# KEYPAD.net
KiCad netlist of a schematic drawn in Altium Designer
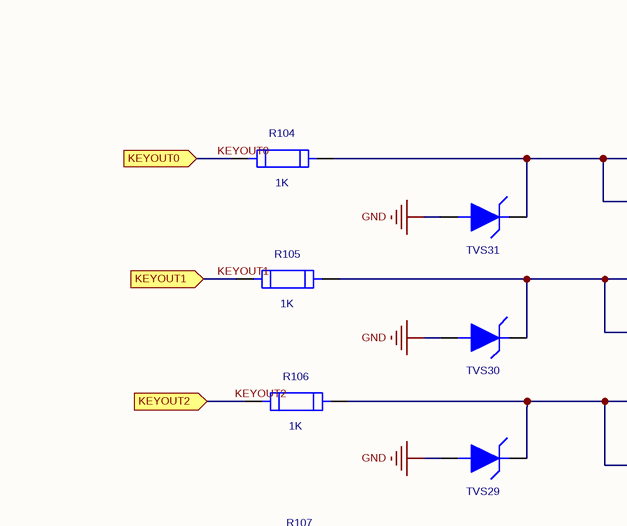
[diagram p0: KEYPAD.SchDoc, top left]
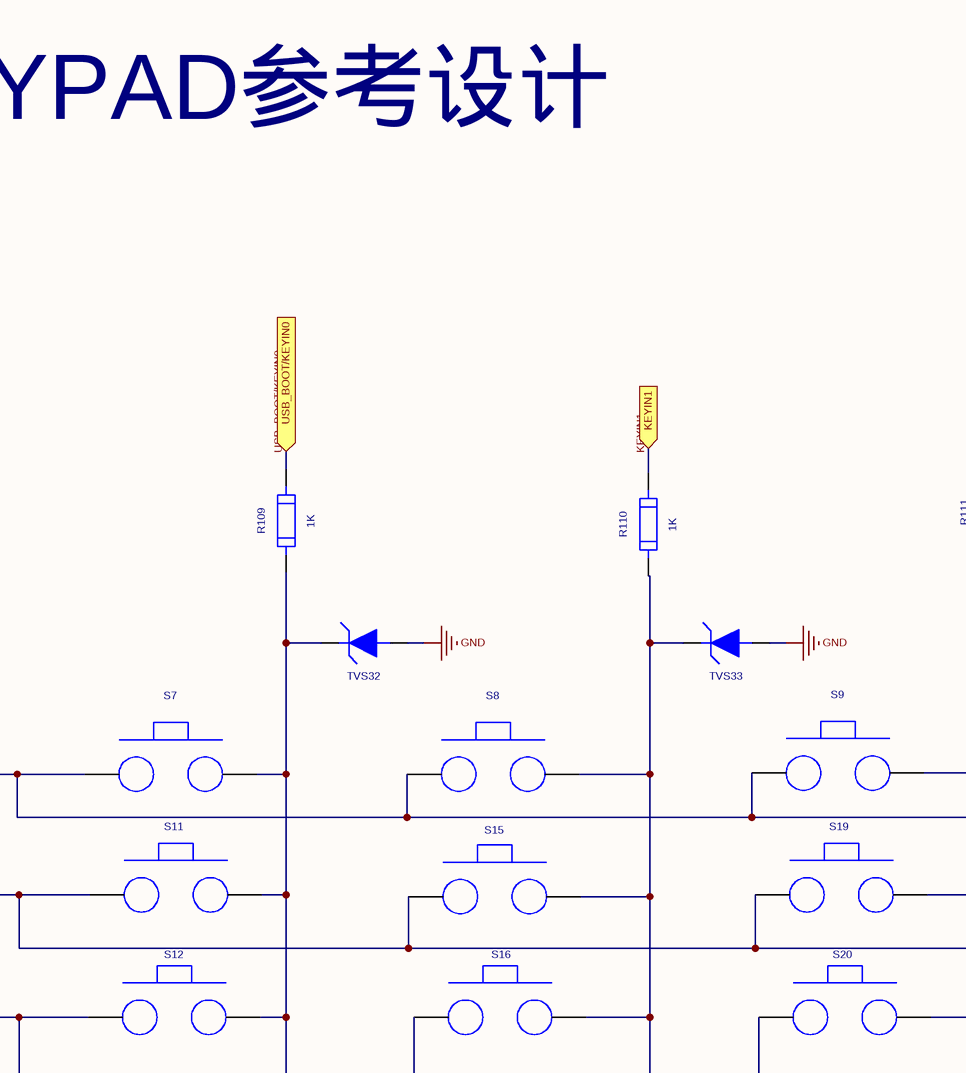
[diagram p1: KEYPAD.SchDoc, top middle]
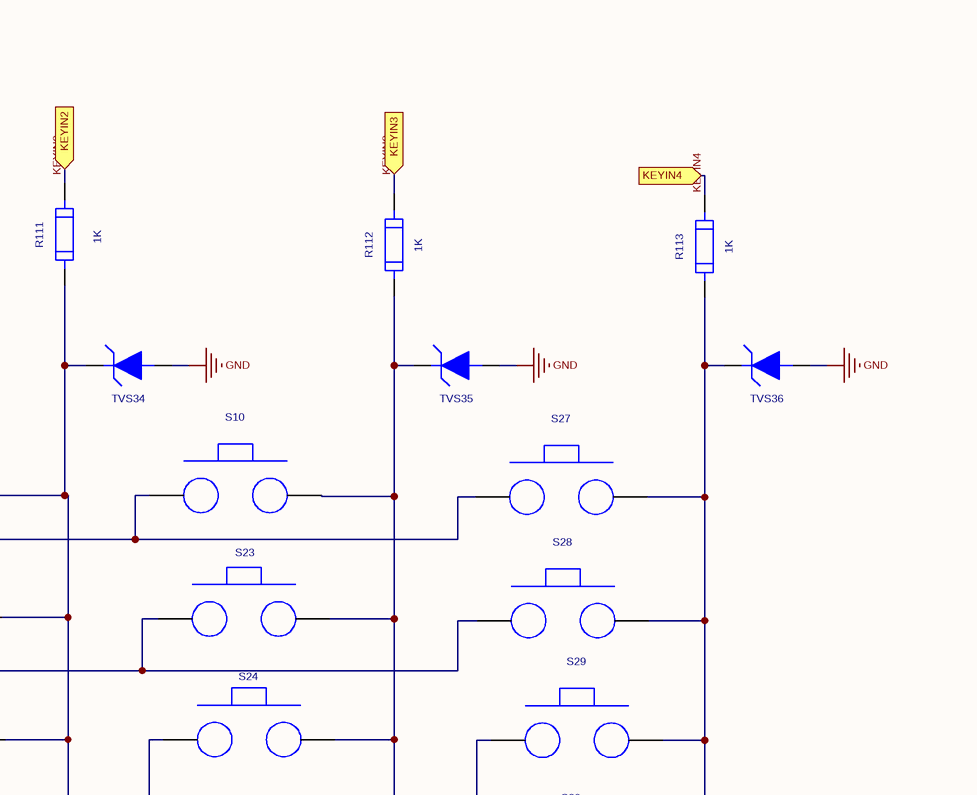
[diagram p2: KEYPAD.SchDoc, top right]
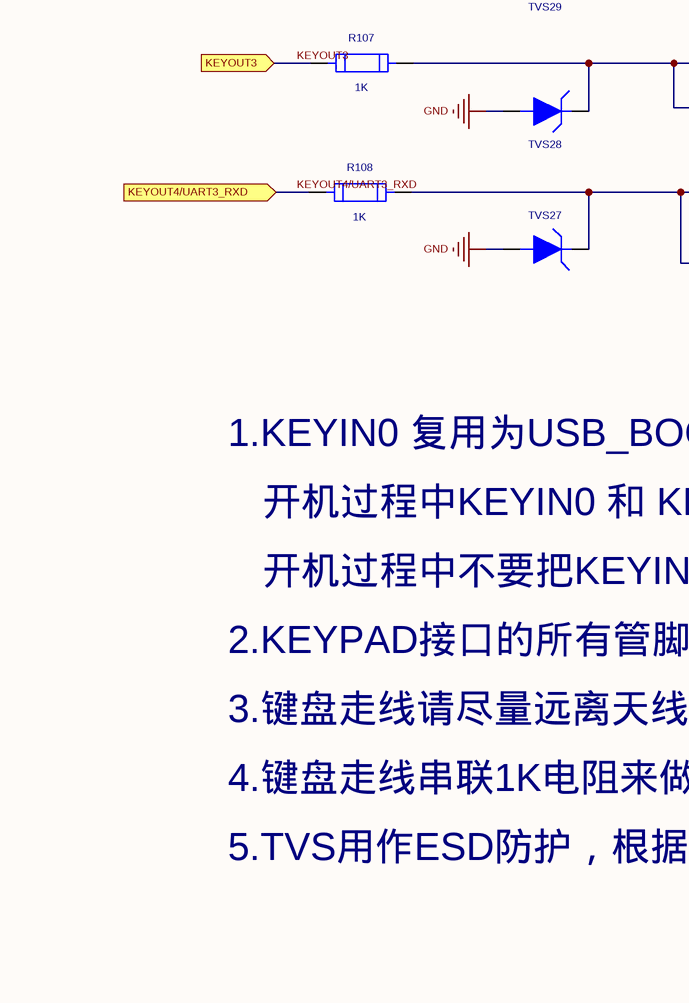
[diagram p3: KEYPAD.SchDoc, bottom left]
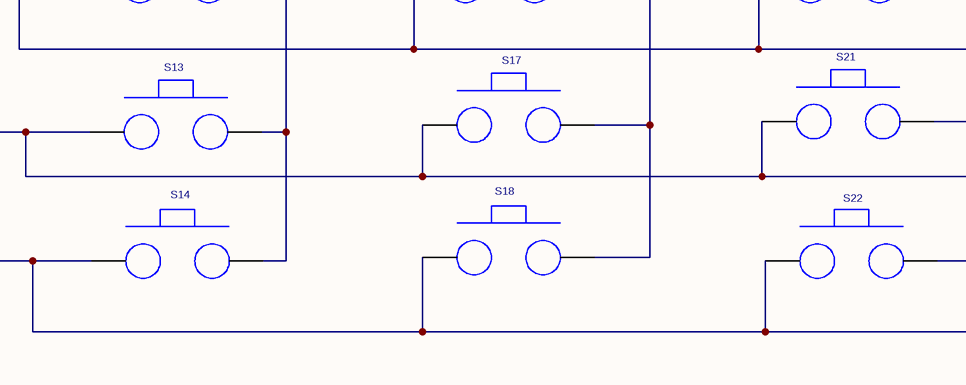
[diagram p4: KEYPAD.SchDoc, bottom middle]
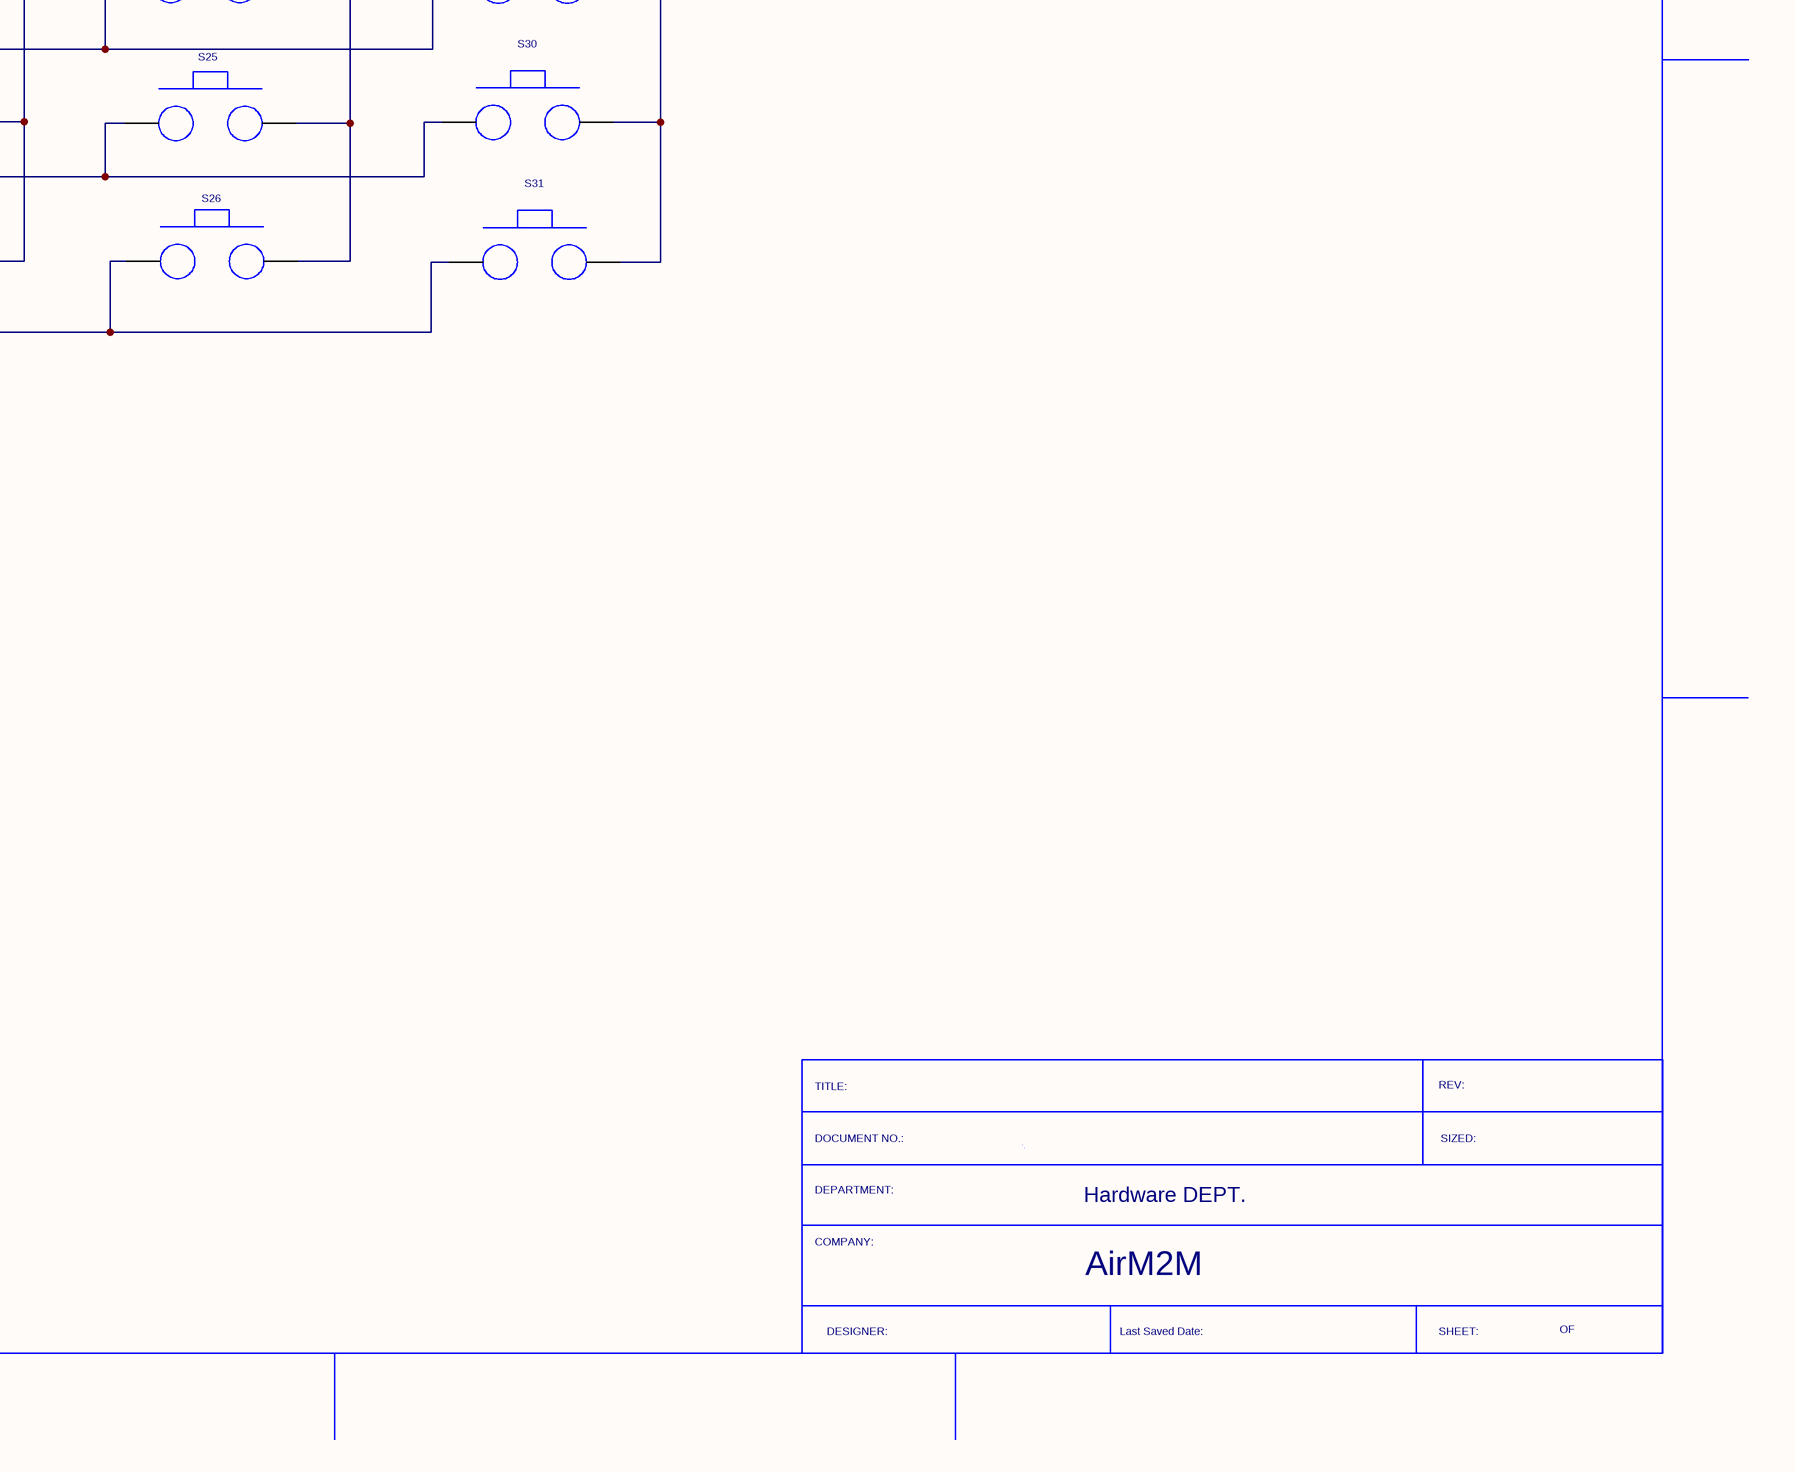
[diagram p5: KEYPAD.SchDoc, bottom right]

(export (version "E")
  (design (tool "Eeschema 10.0.6"))
  (components
    (comp (ref "R104")
      (value "1K")
      (footprint "SR0402")
      (description "RES FILM;1K;+/-1%;1/16W;0402;0.4mm;ROHS")
      (fields (field (name "TOLERANCE") "+/-1%") (field (name "Comment") "RES-1K-+-1%-0402"))
      (libsource (lib "*") (part "RES-1K-+-1%-0402"))
    )
    (comp (ref "R105")
      (value "1K")
      (footprint "SR0402")
      (description "RES FILM;1K;+/-1%;1/16W;0402;0.4mm;ROHS")
      (fields (field (name "TOLERANCE") "+/-1%") (field (name "Comment") "RES-1K-+-1%-0402"))
      (libsource (lib "*") (part "RES-1K-+-1%-0402"))
    )
    (comp (ref "R106")
      (value "1K")
      (footprint "SR0402")
      (description "RES FILM;1K;+/-1%;1/16W;0402;0.4mm;ROHS")
      (fields (field (name "TOLERANCE") "+/-1%") (field (name "Comment") "RES-1K-+-1%-0402"))
      (libsource (lib "*") (part "RES-1K-+-1%-0402"))
    )
    (comp (ref "R107")
      (value "1K")
      (footprint "SR0402")
      (description "RES FILM;1K;+/-1%;1/16W;0402;0.4mm;ROHS")
      (fields (field (name "TOLERANCE") "+/-1%") (field (name "Comment") "RES-1K-+-1%-0402"))
      (libsource (lib "*") (part "RES-1K-+-1%-0402"))
    )
    (comp (ref "R108")
      (value "1K")
      (footprint "SR0402")
      (description "RES FILM;1K;+/-1%;1/16W;0402;0.4mm;ROHS")
      (fields (field (name "TOLERANCE") "+/-1%") (field (name "Comment") "RES-1K-+-1%-0402"))
      (libsource (lib "*") (part "RES-1K-+-1%-0402"))
    )
    (comp (ref "R109")
      (value "1K")
      (footprint "SR0402")
      (description "RES FILM;1K;+/-1%;1/16W;0402;0.4mm;ROHS")
      (fields (field (name "TOLERANCE") "+/-1%") (field (name "Comment") "RES-1K-+-1%-0402"))
      (libsource (lib "*") (part "RES-1K-+-1%-0402"))
    )
    (comp (ref "R110")
      (value "1K")
      (footprint "SR0402")
      (description "RES FILM;1K;+/-1%;1/16W;0402;0.4mm;ROHS")
      (fields (field (name "TOLERANCE") "+/-1%") (field (name "Comment") "RES-1K-+-1%-0402"))
      (libsource (lib "*") (part "RES-1K-+-1%-0402"))
    )
    (comp (ref "R111")
      (value "1K")
      (footprint "SR0402")
      (description "RES FILM;1K;+/-1%;1/16W;0402;0.4mm;ROHS")
      (fields (field (name "TOLERANCE") "+/-1%") (field (name "Comment") "RES-1K-+-1%-0402"))
      (libsource (lib "*") (part "RES-1K-+-1%-0402"))
    )
    (comp (ref "R112")
      (value "1K")
      (footprint "SR0402")
      (description "RES FILM;1K;+/-1%;1/16W;0402;0.4mm;ROHS")
      (fields (field (name "TOLERANCE") "+/-1%") (field (name "Comment") "RES-1K-+-1%-0402"))
      (libsource (lib "*") (part "RES-1K-+-1%-0402"))
    )
    (comp (ref "R113")
      (value "1K")
      (footprint "SR0402")
      (description "RES FILM;1K;+/-1%;1/16W;0402;0.4mm;ROHS")
      (fields (field (name "TOLERANCE") "+/-1%") (field (name "Comment") "RES-1K-+-1%-0402"))
      (libsource (lib "*") (part "RES-1K-+-1%-0402"))
    )
    (comp (ref "S7")
      (value "KEYPAD-D5X5")
      (footprint "KEY55")
      (description "SWITCH-KEYPAD")
      (libsource (lib "*") (part "KEYPAD-D5X5"))
    )
    (comp (ref "S8")
      (value "KEYPAD-D5X5")
      (footprint "KEY55")
      (description "SWITCH-KEYPAD")
      (libsource (lib "*") (part "KEYPAD-D5X5"))
    )
    (comp (ref "S9")
      (value "KEYPAD-D5X5")
      (footprint "KEY55")
      (description "SWITCH-KEYPAD")
      (libsource (lib "*") (part "KEYPAD-D5X5"))
    )
    (comp (ref "S10")
      (value "KEYPAD-D5X5")
      (footprint "KEY55")
      (description "SWITCH-KEYPAD")
      (libsource (lib "*") (part "KEYPAD-D5X5"))
    )
    (comp (ref "S11")
      (value "KEYPAD-D5X5")
      (footprint "KEY55")
      (description "SWITCH-KEYPAD")
      (libsource (lib "*") (part "KEYPAD-D5X5"))
    )
    (comp (ref "S12")
      (value "KEYPAD-D5X5")
      (footprint "KEY55")
      (description "SWITCH-KEYPAD")
      (libsource (lib "*") (part "KEYPAD-D5X5"))
    )
    (comp (ref "S13")
      (value "KEYPAD-D5X5")
      (footprint "KEY55")
      (description "SWITCH-KEYPAD")
      (libsource (lib "*") (part "KEYPAD-D5X5"))
    )
    (comp (ref "S14")
      (value "KEYPAD-D5X5")
      (footprint "KEY55")
      (description "SWITCH-KEYPAD")
      (libsource (lib "*") (part "KEYPAD-D5X5"))
    )
    (comp (ref "S15")
      (value "KEYPAD-D5X5")
      (footprint "KEY55")
      (description "SWITCH-KEYPAD")
      (libsource (lib "*") (part "KEYPAD-D5X5"))
    )
    (comp (ref "S16")
      (value "KEYPAD-D5X5")
      (footprint "KEY55")
      (description "SWITCH-KEYPAD")
      (libsource (lib "*") (part "KEYPAD-D5X5"))
    )
    (comp (ref "S17")
      (value "KEYPAD-D5X5")
      (footprint "KEY55")
      (description "SWITCH-KEYPAD")
      (libsource (lib "*") (part "KEYPAD-D5X5"))
    )
    (comp (ref "S18")
      (value "KEYPAD-D5X5")
      (footprint "KEY55")
      (description "SWITCH-KEYPAD")
      (libsource (lib "*") (part "KEYPAD-D5X5"))
    )
    (comp (ref "S19")
      (value "KEYPAD-D5X5")
      (footprint "KEY55")
      (description "SWITCH-KEYPAD")
      (libsource (lib "*") (part "KEYPAD-D5X5"))
    )
    (comp (ref "S20")
      (value "KEYPAD-D5X5")
      (footprint "KEY55")
      (description "SWITCH-KEYPAD")
      (libsource (lib "*") (part "KEYPAD-D5X5"))
    )
    (comp (ref "S21")
      (value "KEYPAD-D5X5")
      (footprint "KEY55")
      (description "SWITCH-KEYPAD")
      (libsource (lib "*") (part "KEYPAD-D5X5"))
    )
    (comp (ref "S22")
      (value "KEYPAD-D5X5")
      (footprint "KEY55")
      (description "SWITCH-KEYPAD")
      (libsource (lib "*") (part "KEYPAD-D5X5"))
    )
    (comp (ref "S23")
      (value "KEYPAD-D5X5")
      (footprint "KEY55")
      (description "SWITCH-KEYPAD")
      (libsource (lib "*") (part "KEYPAD-D5X5"))
    )
    (comp (ref "S24")
      (value "KEYPAD-D5X5")
      (footprint "KEY55")
      (description "SWITCH-KEYPAD")
      (libsource (lib "*") (part "KEYPAD-D5X5"))
    )
    (comp (ref "S25")
      (value "KEYPAD-D5X5")
      (footprint "KEY55")
      (description "SWITCH-KEYPAD")
      (libsource (lib "*") (part "KEYPAD-D5X5"))
    )
    (comp (ref "S26")
      (value "KEYPAD-D5X5")
      (footprint "KEY55")
      (description "SWITCH-KEYPAD")
      (libsource (lib "*") (part "KEYPAD-D5X5"))
    )
    (comp (ref "S27")
      (value "KEYPAD-D5X5")
      (footprint "KEY55")
      (description "SWITCH-KEYPAD")
      (libsource (lib "*") (part "KEYPAD-D5X5"))
    )
    (comp (ref "S28")
      (value "KEYPAD-D5X5")
      (footprint "KEY55")
      (description "SWITCH-KEYPAD")
      (libsource (lib "*") (part "KEYPAD-D5X5"))
    )
    (comp (ref "S29")
      (value "KEYPAD-D5X5")
      (footprint "KEY55")
      (description "SWITCH-KEYPAD")
      (libsource (lib "*") (part "KEYPAD-D5X5"))
    )
    (comp (ref "S30")
      (value "KEYPAD-D5X5")
      (footprint "KEY55")
      (description "SWITCH-KEYPAD")
      (libsource (lib "*") (part "KEYPAD-D5X5"))
    )
    (comp (ref "S31")
      (value "KEYPAD-D5X5")
      (footprint "KEY55")
      (description "SWITCH-KEYPAD")
      (libsource (lib "*") (part "KEYPAD-D5X5"))
    )
    (comp (ref "TVS27")
      (value "ESD-TVS-ESD9X5.0ST5G")
      (footprint "SOD-923-ESD9X5.0ST5G")
      (description "TVS;5.0V;65PF;SOD?923;ROHS")
      (libsource (lib "*") (part "ESD-TVS-ESD9X5.0ST5G"))
    )
    (comp (ref "TVS28")
      (value "ESD-TVS-ESD9X5.0ST5G")
      (footprint "SOD-923-ESD9X5.0ST5G")
      (description "TVS;5.0V;65PF;SOD?923;ROHS")
      (libsource (lib "*") (part "ESD-TVS-ESD9X5.0ST5G"))
    )
    (comp (ref "TVS29")
      (value "ESD-TVS-ESD9X5.0ST5G")
      (footprint "SOD-923-ESD9X5.0ST5G")
      (description "TVS;5.0V;65PF;SOD?923;ROHS")
      (libsource (lib "*") (part "ESD-TVS-ESD9X5.0ST5G"))
    )
    (comp (ref "TVS30")
      (value "ESD-TVS-ESD9X5.0ST5G")
      (footprint "SOD-923-ESD9X5.0ST5G")
      (description "TVS;5.0V;65PF;SOD?923;ROHS")
      (libsource (lib "*") (part "ESD-TVS-ESD9X5.0ST5G"))
    )
    (comp (ref "TVS31")
      (value "ESD-TVS-ESD9X5.0ST5G")
      (footprint "SOD-923-ESD9X5.0ST5G")
      (description "TVS;5.0V;65PF;SOD?923;ROHS")
      (libsource (lib "*") (part "ESD-TVS-ESD9X5.0ST5G"))
    )
    (comp (ref "TVS32")
      (value "ESD-TVS-ESD9X5.0ST5G")
      (footprint "SOD-923-ESD9X5.0ST5G")
      (description "TVS;5.0V;65PF;SOD?923;ROHS")
      (libsource (lib "*") (part "ESD-TVS-ESD9X5.0ST5G"))
    )
    (comp (ref "TVS33")
      (value "ESD-TVS-ESD9X5.0ST5G")
      (footprint "SOD-923-ESD9X5.0ST5G")
      (description "TVS;5.0V;65PF;SOD?923;ROHS")
      (libsource (lib "*") (part "ESD-TVS-ESD9X5.0ST5G"))
    )
    (comp (ref "TVS34")
      (value "ESD-TVS-ESD9X5.0ST5G")
      (footprint "SOD-923-ESD9X5.0ST5G")
      (description "TVS;5.0V;65PF;SOD?923;ROHS")
      (libsource (lib "*") (part "ESD-TVS-ESD9X5.0ST5G"))
    )
    (comp (ref "TVS35")
      (value "ESD-TVS-ESD9X5.0ST5G")
      (footprint "SOD-923-ESD9X5.0ST5G")
      (description "TVS;5.0V;65PF;SOD?923;ROHS")
      (libsource (lib "*") (part "ESD-TVS-ESD9X5.0ST5G"))
    )
    (comp (ref "TVS36")
      (value "ESD-TVS-ESD9X5.0ST5G")
      (footprint "SOD-923-ESD9X5.0ST5G")
      (description "TVS;5.0V;65PF;SOD?923;ROHS")
      (libsource (lib "*") (part "ESD-TVS-ESD9X5.0ST5G"))
    )
  )
  (nets
    (net (code "1") (name "/KEYIN1") (class "Default")
      (node (ref "R110") (pin "2") (pinfunction "2_2") (pintype "passive"))
    )
    (net (code "2") (name "/KEYIN2") (class "Default")
      (node (ref "R111") (pin "2") (pinfunction "2_2") (pintype "passive"))
    )
    (net (code "3") (name "/KEYIN3") (class "Default")
      (node (ref "R112") (pin "2") (pinfunction "2_2") (pintype "passive"))
    )
    (net (code "4") (name "/KEYIN4") (class "Default")
      (node (ref "R113") (pin "2") (pinfunction "2_2") (pintype "passive"))
    )
    (net (code "5") (name "/KEYOUT0") (class "Default")
      (node (ref "R104") (pin "1") (pinfunction "1_1") (pintype "passive"))
    )
    (net (code "6") (name "/KEYOUT1") (class "Default")
      (node (ref "R105") (pin "1") (pinfunction "1_1") (pintype "passive"))
    )
    (net (code "7") (name "/KEYOUT2") (class "Default")
      (node (ref "R106") (pin "1") (pinfunction "1_1") (pintype "passive"))
    )
    (net (code "8") (name "/KEYOUT3") (class "Default")
      (node (ref "R107") (pin "1") (pinfunction "1_1") (pintype "passive"))
    )
    (net (code "9") (name "/KEYOUT4{slash}UART3_RXD") (class "Default")
      (node (ref "R108") (pin "1") (pinfunction "1_1") (pintype "passive"))
    )
    (net (code "10") (name "/USB_BOOT{slash}KEYIN0") (class "Default")
      (node (ref "R109") (pin "2") (pinfunction "2_2") (pintype "passive"))
    )
    (net (code "11") (name "GND") (class "Default")
      (node (ref "TVS27") (pin "2") (pinfunction "2_2") (pintype "passive"))
      (node (ref "TVS28") (pin "2") (pinfunction "2_2") (pintype "passive"))
      (node (ref "TVS29") (pin "2") (pinfunction "2_2") (pintype "passive"))
      (node (ref "TVS30") (pin "2") (pinfunction "2_2") (pintype "passive"))
      (node (ref "TVS31") (pin "2") (pinfunction "2_2") (pintype "passive"))
      (node (ref "TVS32") (pin "2") (pinfunction "2_2") (pintype "passive"))
      (node (ref "TVS33") (pin "2") (pinfunction "2_2") (pintype "passive"))
      (node (ref "TVS34") (pin "2") (pinfunction "2_2") (pintype "passive"))
      (node (ref "TVS35") (pin "2") (pinfunction "2_2") (pintype "passive"))
      (node (ref "TVS36") (pin "2") (pinfunction "2_2") (pintype "passive"))
    )
    (net (code "12") (name "Net-(R104-Pad2)") (class "Default")
      (node (ref "R104") (pin "2") (pinfunction "2_2") (pintype "passive"))
      (node (ref "S10") (pin "1") (pinfunction "1_1") (pintype "passive"))
      (node (ref "S27") (pin "1") (pinfunction "1_1") (pintype "passive"))
      (node (ref "S7") (pin "1") (pinfunction "1_1") (pintype "passive"))
      (node (ref "S8") (pin "1") (pinfunction "1_1") (pintype "passive"))
      (node (ref "S9") (pin "1") (pinfunction "1_1") (pintype "passive"))
      (node (ref "TVS31") (pin "1") (pinfunction "1_1") (pintype "passive"))
    )
    (net (code "13") (name "Net-(R105-Pad2)") (class "Default")
      (node (ref "R105") (pin "2") (pinfunction "2_2") (pintype "passive"))
      (node (ref "S11") (pin "1") (pinfunction "1_1") (pintype "passive"))
      (node (ref "S15") (pin "1") (pinfunction "1_1") (pintype "passive"))
      (node (ref "S19") (pin "1") (pinfunction "1_1") (pintype "passive"))
      (node (ref "S23") (pin "1") (pinfunction "1_1") (pintype "passive"))
      (node (ref "S28") (pin "1") (pinfunction "1_1") (pintype "passive"))
      (node (ref "TVS30") (pin "1") (pinfunction "1_1") (pintype "passive"))
    )
    (net (code "14") (name "Net-(R106-Pad2)") (class "Default")
      (node (ref "R106") (pin "2") (pinfunction "2_2") (pintype "passive"))
      (node (ref "S12") (pin "1") (pinfunction "1_1") (pintype "passive"))
      (node (ref "S16") (pin "1") (pinfunction "1_1") (pintype "passive"))
      (node (ref "S20") (pin "1") (pinfunction "1_1") (pintype "passive"))
      (node (ref "S24") (pin "1") (pinfunction "1_1") (pintype "passive"))
      (node (ref "S29") (pin "1") (pinfunction "1_1") (pintype "passive"))
      (node (ref "TVS29") (pin "1") (pinfunction "1_1") (pintype "passive"))
    )
    (net (code "15") (name "Net-(R107-Pad2)") (class "Default")
      (node (ref "R107") (pin "2") (pinfunction "2_2") (pintype "passive"))
      (node (ref "S13") (pin "1") (pinfunction "1_1") (pintype "passive"))
      (node (ref "S17") (pin "1") (pinfunction "1_1") (pintype "passive"))
      (node (ref "S21") (pin "1") (pinfunction "1_1") (pintype "passive"))
      (node (ref "S25") (pin "1") (pinfunction "1_1") (pintype "passive"))
      (node (ref "S30") (pin "1") (pinfunction "1_1") (pintype "passive"))
      (node (ref "TVS28") (pin "1") (pinfunction "1_1") (pintype "passive"))
    )
    (net (code "16") (name "Net-(R108-Pad2)") (class "Default")
      (node (ref "R108") (pin "2") (pinfunction "2_2") (pintype "passive"))
      (node (ref "S14") (pin "1") (pinfunction "1_1") (pintype "passive"))
      (node (ref "S18") (pin "1") (pinfunction "1_1") (pintype "passive"))
      (node (ref "S22") (pin "1") (pinfunction "1_1") (pintype "passive"))
      (node (ref "S26") (pin "1") (pinfunction "1_1") (pintype "passive"))
      (node (ref "S31") (pin "1") (pinfunction "1_1") (pintype "passive"))
      (node (ref "TVS27") (pin "1") (pinfunction "1_1") (pintype "passive"))
    )
    (net (code "17") (name "Net-(R109-Pad1)") (class "Default")
      (node (ref "R109") (pin "1") (pinfunction "1_1") (pintype "passive"))
      (node (ref "S11") (pin "2") (pinfunction "2_2") (pintype "passive"))
      (node (ref "S12") (pin "2") (pinfunction "2_2") (pintype "passive"))
      (node (ref "S13") (pin "2") (pinfunction "2_2") (pintype "passive"))
      (node (ref "S14") (pin "2") (pinfunction "2_2") (pintype "passive"))
      (node (ref "S7") (pin "2") (pinfunction "2_2") (pintype "passive"))
      (node (ref "TVS32") (pin "1") (pinfunction "1_1") (pintype "passive"))
    )
    (net (code "18") (name "Net-(R110-Pad1)") (class "Default")
      (node (ref "R110") (pin "1") (pinfunction "1_1") (pintype "passive"))
      (node (ref "S15") (pin "2") (pinfunction "2_2") (pintype "passive"))
      (node (ref "S16") (pin "2") (pinfunction "2_2") (pintype "passive"))
      (node (ref "S17") (pin "2") (pinfunction "2_2") (pintype "passive"))
      (node (ref "S18") (pin "2") (pinfunction "2_2") (pintype "passive"))
      (node (ref "S8") (pin "2") (pinfunction "2_2") (pintype "passive"))
      (node (ref "TVS33") (pin "1") (pinfunction "1_1") (pintype "passive"))
    )
    (net (code "19") (name "Net-(R111-Pad1)") (class "Default")
      (node (ref "R111") (pin "1") (pinfunction "1_1") (pintype "passive"))
      (node (ref "S19") (pin "2") (pinfunction "2_2") (pintype "passive"))
      (node (ref "S20") (pin "2") (pinfunction "2_2") (pintype "passive"))
      (node (ref "S21") (pin "2") (pinfunction "2_2") (pintype "passive"))
      (node (ref "S22") (pin "2") (pinfunction "2_2") (pintype "passive"))
      (node (ref "S9") (pin "2") (pinfunction "2_2") (pintype "passive"))
      (node (ref "TVS34") (pin "1") (pinfunction "1_1") (pintype "passive"))
    )
    (net (code "20") (name "Net-(R112-Pad1)") (class "Default")
      (node (ref "R112") (pin "1") (pinfunction "1_1") (pintype "passive"))
      (node (ref "S10") (pin "2") (pinfunction "2_2") (pintype "passive"))
      (node (ref "S23") (pin "2") (pinfunction "2_2") (pintype "passive"))
      (node (ref "S24") (pin "2") (pinfunction "2_2") (pintype "passive"))
      (node (ref "S25") (pin "2") (pinfunction "2_2") (pintype "passive"))
      (node (ref "S26") (pin "2") (pinfunction "2_2") (pintype "passive"))
      (node (ref "TVS35") (pin "1") (pinfunction "1_1") (pintype "passive"))
    )
    (net (code "21") (name "Net-(R113-Pad1)") (class "Default")
      (node (ref "R113") (pin "1") (pinfunction "1_1") (pintype "passive"))
      (node (ref "S27") (pin "2") (pinfunction "2_2") (pintype "passive"))
      (node (ref "S28") (pin "2") (pinfunction "2_2") (pintype "passive"))
      (node (ref "S29") (pin "2") (pinfunction "2_2") (pintype "passive"))
      (node (ref "S30") (pin "2") (pinfunction "2_2") (pintype "passive"))
      (node (ref "S31") (pin "2") (pinfunction "2_2") (pintype "passive"))
      (node (ref "TVS36") (pin "1") (pinfunction "1_1") (pintype "passive"))
    )
  )
)
